# nrf24prominiadapter.net
KiCad netlist of a schematic drawn in EAGLE
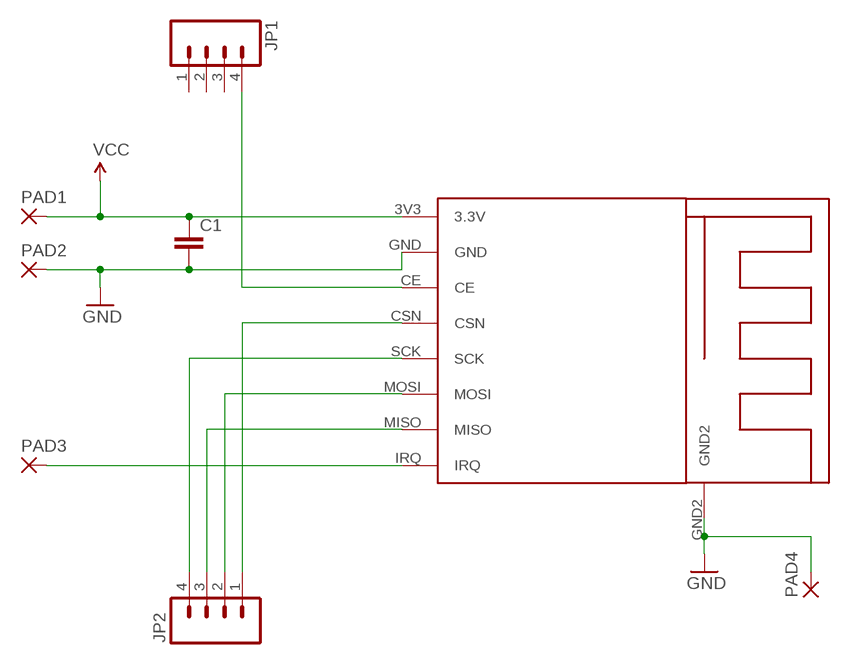
[diagram p0: schematic, sheet 1]

(export (version "E")
  (design (tool "Eeschema 10.0.6"))
  (components
    (comp (ref "C1")
      (value "C-EUC0805")
      (footprint "eagle-import:C0805")
      (libsource (lib "eagle-import") (part "C-EUC0805"))
    )
    (comp (ref "JP1")
      (value "M04NO_SILK_ALL_ROUND")
      (footprint "eagle-import:1X04_NO_SILK_ALL_ROUND")
      (libsource (lib "eagle-import") (part "M04NO_SILK_ALL_ROUND"))
    )
    (comp (ref "JP2")
      (value "M04NO_SILK_ALL_ROUND")
      (footprint "eagle-import:1X04_NO_SILK_ALL_ROUND")
      (libsource (lib "eagle-import") (part "M04NO_SILK_ALL_ROUND"))
    )
    (comp (ref "PAD1")
      (value "SMD2")
      (footprint "eagle-import:SMD1,27-2,54")
      (libsource (lib "eagle-import") (part "SMD2"))
    )
    (comp (ref "PAD2")
      (value "SMD2")
      (footprint "eagle-import:SMD1,27-2,54")
      (libsource (lib "eagle-import") (part "SMD2"))
    )
    (comp (ref "PAD3")
      (value "SMD2")
      (footprint "eagle-import:SMD1,27-2,54")
      (libsource (lib "eagle-import") (part "SMD2"))
    )
    (comp (ref "PAD4")
      (value "SMD2")
      (footprint "eagle-import:SMD1,27-2,54")
      (libsource (lib "eagle-import") (part "SMD2"))
    )
    (comp (ref "U$1")
      (value "NRF24MINI")
      (footprint "eagle-import:NRF24MINI")
      (libsource (lib "eagle-import") (part "NRF24MINI"))
    )
  )
  (nets
    (net (code "1") (name "GND") (class "Default")
      (node (ref "C1") (pin "2") (pinfunction "2_2") (pintype "passive"))
      (node (ref "PAD2") (pin "1") (pinfunction "P_1") (pintype "passive"))
      (node (ref "PAD4") (pin "1") (pinfunction "P_1") (pintype "passive"))
      (node (ref "U$1") (pin "GND") (pinfunction "GND_GND") (pintype "bidirectional"))
      (node (ref "U$1") (pin "GND2") (pinfunction "GND2_GND2") (pintype "bidirectional"))
    )
    (net (code "2") (name "Net-(JP1-Pad4)") (class "Default")
      (node (ref "JP1") (pin "4") (pinfunction "4_4") (pintype "passive"))
      (node (ref "U$1") (pin "CE") (pinfunction "CE_CE") (pintype "bidirectional"))
    )
    (net (code "3") (name "Net-(JP2-Pad1)") (class "Default")
      (node (ref "JP2") (pin "1") (pinfunction "1_1") (pintype "passive"))
      (node (ref "U$1") (pin "CSN") (pinfunction "CSN_CSN") (pintype "bidirectional"))
    )
    (net (code "4") (name "Net-(JP2-Pad2)") (class "Default")
      (node (ref "JP2") (pin "2") (pinfunction "2_2") (pintype "passive"))
      (node (ref "U$1") (pin "MOSI") (pinfunction "MOSI_MOSI") (pintype "bidirectional"))
    )
    (net (code "5") (name "Net-(JP2-Pad3)") (class "Default")
      (node (ref "JP2") (pin "3") (pinfunction "3_3") (pintype "passive"))
      (node (ref "U$1") (pin "MISO") (pinfunction "MISO_MISO") (pintype "bidirectional"))
    )
    (net (code "6") (name "Net-(JP2-Pad4)") (class "Default")
      (node (ref "JP2") (pin "4") (pinfunction "4_4") (pintype "passive"))
      (node (ref "U$1") (pin "SCK") (pinfunction "SCK_SCK") (pintype "bidirectional"))
    )
    (net (code "7") (name "Net-(PAD3-P)") (class "Default")
      (node (ref "PAD3") (pin "1") (pinfunction "P_1") (pintype "passive"))
      (node (ref "U$1") (pin "IRQ") (pinfunction "IRQ_IRQ") (pintype "bidirectional"))
    )
    (net (code "8") (name "VCC") (class "Default")
      (node (ref "C1") (pin "1") (pinfunction "1_1") (pintype "passive"))
      (node (ref "PAD1") (pin "1") (pinfunction "P_1") (pintype "passive"))
      (node (ref "U$1") (pin "3V3") (pinfunction "3.3V_3V3") (pintype "bidirectional"))
    )
    (net (code "9") (name "unconnected-(JP1-Pad1)") (class "Default")
      (node (ref "JP1") (pin "1") (pinfunction "1_1") (pintype "passive"))
    )
    (net (code "10") (name "unconnected-(JP1-Pad2)") (class "Default")
      (node (ref "JP1") (pin "2") (pinfunction "2_2") (pintype "passive"))
    )
    (net (code "11") (name "unconnected-(JP1-Pad3)") (class "Default")
      (node (ref "JP1") (pin "3") (pinfunction "3_3") (pintype "passive"))
    )
  )
)
